# Knives_Controls.net
KiCad netlist of a schematic drawn in EAGLE
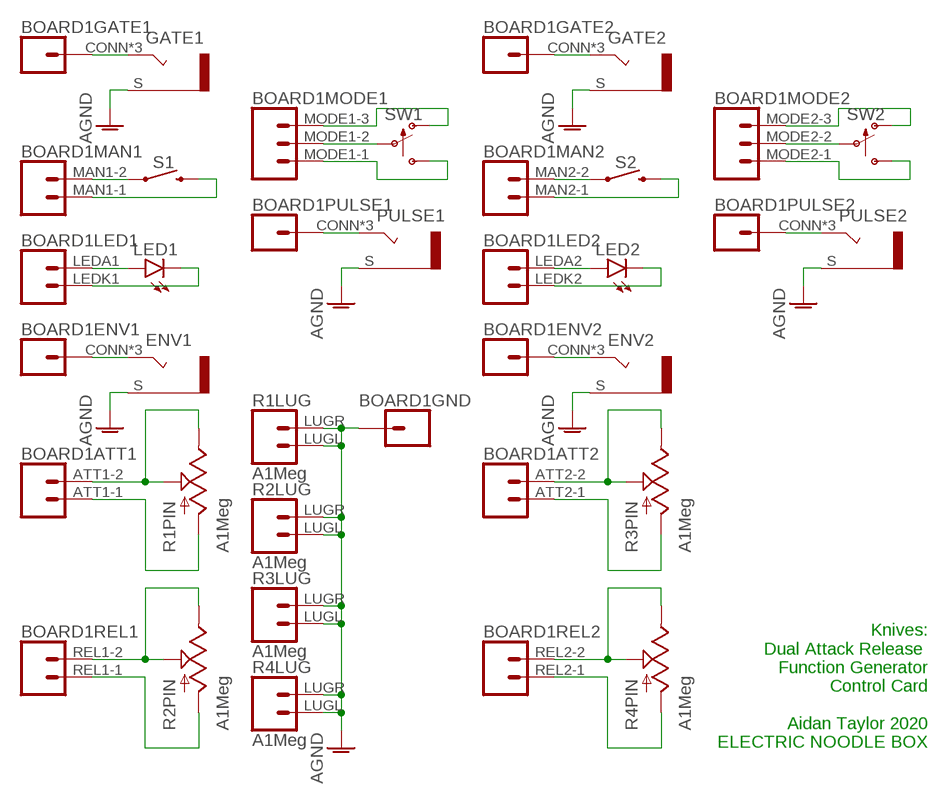
[diagram p0: schematic, sheet 1]

(export (version "E")
  (design (tool "Eeschema 10.0.6"))
  (components
    (comp (ref "BOARD1")
      (value "KNIVES_LINK")
      (footprint "eagle-import:KNIVES")
      (libsource (lib "eagle-import") (part "KNIVES_LINK"))
    )
    (comp (ref "ENV1")
      (value "COMBI-JACKCINCHNANA")
      (footprint "eagle-import:NEWCOMBOJACK_PANEL")
      (libsource (lib "eagle-import") (part "COMBI-JACKCINCHNANA"))
    )
    (comp (ref "ENV2")
      (value "COMBI-JACKCINCHNANA")
      (footprint "eagle-import:NEWCOMBOJACK_PANEL")
      (libsource (lib "eagle-import") (part "COMBI-JACKCINCHNANA"))
    )
    (comp (ref "GATE1")
      (value "COMBI-JACKCINCHNANA")
      (footprint "eagle-import:NEWCOMBOJACK_PANEL")
      (libsource (lib "eagle-import") (part "COMBI-JACKCINCHNANA"))
    )
    (comp (ref "GATE2")
      (value "COMBI-JACKCINCHNANA")
      (footprint "eagle-import:NEWCOMBOJACK_PANEL")
      (libsource (lib "eagle-import") (part "COMBI-JACKCINCHNANA"))
    )
    (comp (ref "LED1")
      (value "LED3MM")
      (footprint "eagle-import:LED3MM")
      (libsource (lib "eagle-import") (part "LED3MM"))
    )
    (comp (ref "LED2")
      (value "LED3MM")
      (footprint "eagle-import:LED3MM")
      (libsource (lib "eagle-import") (part "LED3MM"))
    )
    (comp (ref "PULSE1")
      (value "COMBI-JACKCINCHNANA")
      (footprint "eagle-import:NEWCOMBOJACK_PANEL")
      (libsource (lib "eagle-import") (part "COMBI-JACKCINCHNANA"))
    )
    (comp (ref "PULSE2")
      (value "COMBI-JACKCINCHNANA")
      (footprint "eagle-import:NEWCOMBOJACK_PANEL")
      (libsource (lib "eagle-import") (part "COMBI-JACKCINCHNANA"))
    )
    (comp (ref "R1")
      (value "A1Meg")
      (footprint "eagle-import:ALPHA_RV09_9MMPOT")
      (libsource (lib "eagle-import") (part "POTENTIOMETER"))
    )
    (comp (ref "R2")
      (value "A1Meg")
      (footprint "eagle-import:ALPHA_RV09_9MMPOT")
      (libsource (lib "eagle-import") (part "POTENTIOMETER"))
    )
    (comp (ref "R3")
      (value "A1Meg")
      (footprint "eagle-import:ALPHA_RV09_9MMPOT")
      (libsource (lib "eagle-import") (part "POTENTIOMETER"))
    )
    (comp (ref "R4")
      (value "A1Meg")
      (footprint "eagle-import:ALPHA_RV09_9MMPOT")
      (libsource (lib "eagle-import") (part "POTENTIOMETER"))
    )
    (comp (ref "S1")
      (value "MCDTS-2_PUSHBUTTON")
      (footprint "eagle-import:MCDTS-2_PUSHBUTTON")
      (libsource (lib "eagle-import") (part "MCDTS-2_PUSHBUTTON"))
    )
    (comp (ref "S2")
      (value "MCDTS-2_PUSHBUTTON")
      (footprint "eagle-import:MCDTS-2_PUSHBUTTON")
      (libsource (lib "eagle-import") (part "MCDTS-2_PUSHBUTTON"))
    )
    (comp (ref "SW1")
      (value "SPDT_SWITCHDW1")
      (footprint "eagle-import:MICRODPDT-DW1")
      (libsource (lib "eagle-import") (part "SPDT_SWITCHDW1"))
    )
    (comp (ref "SW2")
      (value "SPDT_SWITCHDW1")
      (footprint "eagle-import:MICRODPDT-DW1")
      (libsource (lib "eagle-import") (part "SPDT_SWITCHDW1"))
    )
  )
  (nets
    (net (code "1") (name "AGND") (class "Default")
      (node (ref "BOARD1") (pin "GND") (pinfunction "1_GND") (pintype "passive"))
      (node (ref "ENV1") (pin "S") (pinfunction "S_S") (pintype "passive"))
      (node (ref "ENV2") (pin "S") (pinfunction "S_S") (pintype "passive"))
      (node (ref "GATE1") (pin "S") (pinfunction "S_S") (pintype "passive"))
      (node (ref "GATE2") (pin "S") (pinfunction "S_S") (pintype "passive"))
      (node (ref "PULSE1") (pin "S") (pinfunction "S_S") (pintype "passive"))
      (node (ref "PULSE2") (pin "S") (pinfunction "S_S") (pintype "passive"))
      (node (ref "R1") (pin "LUGL") (pinfunction "1_LUGL") (pintype "passive"))
      (node (ref "R1") (pin "LUGR") (pinfunction "2_LUGR") (pintype "passive"))
      (node (ref "R2") (pin "LUGL") (pinfunction "1_LUGL") (pintype "passive"))
      (node (ref "R2") (pin "LUGR") (pinfunction "2_LUGR") (pintype "passive"))
      (node (ref "R3") (pin "LUGL") (pinfunction "1_LUGL") (pintype "passive"))
      (node (ref "R3") (pin "LUGR") (pinfunction "2_LUGR") (pintype "passive"))
      (node (ref "R4") (pin "LUGL") (pinfunction "1_LUGL") (pintype "passive"))
      (node (ref "R4") (pin "LUGR") (pinfunction "2_LUGR") (pintype "passive"))
    )
    (net (code "2") (name "Net-(BOARD1A-1)") (class "Default")
      (node (ref "BOARD1") (pin "ATT1-1") (pinfunction "1_ATT1-1") (pintype "passive"))
      (node (ref "R1") (pin "C1") (pinfunction "A_C1") (pintype "passive"))
    )
    (net (code "3") (name "Net-(BOARD1A-2)") (class "Default")
      (node (ref "BOARD1") (pin "ATT1-2") (pinfunction "2_ATT1-2") (pintype "passive"))
      (node (ref "R1") (pin "C2") (pinfunction "W_C2") (pintype "passive"))
      (node (ref "R1") (pin "C3") (pinfunction "B_C3") (pintype "passive"))
    )
    (net (code "4") (name "Net-(BOARD1B-1)") (class "Default")
      (node (ref "BOARD1") (pin "ATT2-1") (pinfunction "1_ATT2-1") (pintype "passive"))
      (node (ref "R3") (pin "C1") (pinfunction "A_C1") (pintype "passive"))
    )
    (net (code "5") (name "Net-(BOARD1B-2)") (class "Default")
      (node (ref "BOARD1") (pin "ATT2-2") (pinfunction "2_ATT2-2") (pintype "passive"))
      (node (ref "R3") (pin "C2") (pinfunction "W_C2") (pintype "passive"))
      (node (ref "R3") (pin "C3") (pinfunction "B_C3") (pintype "passive"))
    )
    (net (code "6") (name "Net-(BOARD1C-1)") (class "Default")
      (node (ref "BOARD1") (pin "EOUT1") (pinfunction "1_EOUT1") (pintype "passive"))
      (node (ref "ENV1") (pin "CONN") (pinfunction "T_CONN") (pintype "passive"))
      (node (ref "ENV1") (pin "T1") (pinfunction "T_T1") (pintype "passive"))
      (node (ref "ENV1") (pin "T2") (pinfunction "T_T2") (pintype "passive"))
    )
    (net (code "7") (name "Net-(BOARD1D-1)") (class "Default")
      (node (ref "BOARD1") (pin "EOUT2") (pinfunction "1_EOUT2") (pintype "passive"))
      (node (ref "ENV2") (pin "CONN") (pinfunction "T_CONN") (pintype "passive"))
      (node (ref "ENV2") (pin "T1") (pinfunction "T_T1") (pintype "passive"))
      (node (ref "ENV2") (pin "T2") (pinfunction "T_T2") (pintype "passive"))
    )
    (net (code "8") (name "Net-(BOARD1E-1)") (class "Default")
      (node (ref "BOARD1") (pin "G1") (pinfunction "1_G1") (pintype "passive"))
      (node (ref "GATE1") (pin "CONN") (pinfunction "T_CONN") (pintype "passive"))
      (node (ref "GATE1") (pin "T1") (pinfunction "T_T1") (pintype "passive"))
      (node (ref "GATE1") (pin "T2") (pinfunction "T_T2") (pintype "passive"))
    )
    (net (code "9") (name "Net-(BOARD1F-1)") (class "Default")
      (node (ref "BOARD1") (pin "G2") (pinfunction "1_G2") (pintype "passive"))
      (node (ref "GATE2") (pin "CONN") (pinfunction "T_CONN") (pintype "passive"))
      (node (ref "GATE2") (pin "T1") (pinfunction "T_T1") (pintype "passive"))
      (node (ref "GATE2") (pin "T2") (pinfunction "T_T2") (pintype "passive"))
    )
    (net (code "10") (name "Net-(BOARD1H-1)") (class "Default")
      (node (ref "BOARD1") (pin "LEDK1") (pinfunction "1_LEDK1") (pintype "passive"))
      (node (ref "LED1") (pin "K") (pinfunction "C_K") (pintype "passive"))
    )
    (net (code "11") (name "Net-(BOARD1H-2)") (class "Default")
      (node (ref "BOARD1") (pin "LEDA1") (pinfunction "2_LEDA1") (pintype "passive"))
      (node (ref "LED1") (pin "A") (pinfunction "A_A") (pintype "passive"))
    )
    (net (code "12") (name "Net-(BOARD1I-1)") (class "Default")
      (node (ref "BOARD1") (pin "LEDK2") (pinfunction "1_LEDK2") (pintype "passive"))
      (node (ref "LED2") (pin "K") (pinfunction "C_K") (pintype "passive"))
    )
    (net (code "13") (name "Net-(BOARD1I-2)") (class "Default")
      (node (ref "BOARD1") (pin "LEDA2") (pinfunction "2_LEDA2") (pintype "passive"))
      (node (ref "LED2") (pin "A") (pinfunction "A_A") (pintype "passive"))
    )
    (net (code "14") (name "Net-(BOARD1J-1)") (class "Default")
      (node (ref "BOARD1") (pin "MAN1-1") (pinfunction "1_MAN1-1") (pintype "passive"))
      (node (ref "S1") (pin "P$3") (pinfunction "2_P$3") (pintype "passive"))
      (node (ref "S1") (pin "P$4") (pinfunction "2_P$4") (pintype "passive"))
    )
    (net (code "15") (name "Net-(BOARD1J-2)") (class "Default")
      (node (ref "BOARD1") (pin "MAN1-2") (pinfunction "2_MAN1-2") (pintype "passive"))
      (node (ref "S1") (pin "P$1") (pinfunction "1_P$1") (pintype "passive"))
      (node (ref "S1") (pin "P$2") (pinfunction "1_P$2") (pintype "passive"))
    )
    (net (code "16") (name "Net-(BOARD1K-1)") (class "Default")
      (node (ref "BOARD1") (pin "MAN2-1") (pinfunction "1_MAN2-1") (pintype "passive"))
      (node (ref "S2") (pin "P$3") (pinfunction "2_P$3") (pintype "passive"))
      (node (ref "S2") (pin "P$4") (pinfunction "2_P$4") (pintype "passive"))
    )
    (net (code "17") (name "Net-(BOARD1K-2)") (class "Default")
      (node (ref "BOARD1") (pin "MAN2-2") (pinfunction "2_MAN2-2") (pintype "passive"))
      (node (ref "S2") (pin "P$1") (pinfunction "1_P$1") (pintype "passive"))
      (node (ref "S2") (pin "P$2") (pinfunction "1_P$2") (pintype "passive"))
    )
    (net (code "18") (name "Net-(BOARD1L-1)") (class "Default")
      (node (ref "BOARD1") (pin "MODE1-1") (pinfunction "1_MODE1-1") (pintype "passive"))
      (node (ref "SW1") (pin "C3") (pinfunction "S_C3") (pintype "passive"))
    )
    (net (code "19") (name "Net-(BOARD1L-2)") (class "Default")
      (node (ref "BOARD1") (pin "MODE1-2") (pinfunction "2_MODE1-2") (pintype "passive"))
      (node (ref "SW1") (pin "C2") (pinfunction "P_C2") (pintype "passive"))
    )
    (net (code "20") (name "Net-(BOARD1L-3)") (class "Default")
      (node (ref "BOARD1") (pin "MODE1-3") (pinfunction "3_MODE1-3") (pintype "passive"))
      (node (ref "SW1") (pin "C1") (pinfunction "O_C1") (pintype "passive"))
    )
    (net (code "21") (name "Net-(BOARD1M-1)") (class "Default")
      (node (ref "BOARD1") (pin "MODE2-1") (pinfunction "1_MODE2-1") (pintype "passive"))
      (node (ref "SW2") (pin "C3") (pinfunction "S_C3") (pintype "passive"))
    )
    (net (code "22") (name "Net-(BOARD1M-2)") (class "Default")
      (node (ref "BOARD1") (pin "MODE2-2") (pinfunction "2_MODE2-2") (pintype "passive"))
      (node (ref "SW2") (pin "C2") (pinfunction "P_C2") (pintype "passive"))
    )
    (net (code "23") (name "Net-(BOARD1M-3)") (class "Default")
      (node (ref "BOARD1") (pin "MODE2-3") (pinfunction "3_MODE2-3") (pintype "passive"))
      (node (ref "SW2") (pin "C1") (pinfunction "O_C1") (pintype "passive"))
    )
    (net (code "24") (name "Net-(BOARD1N-1)") (class "Default")
      (node (ref "BOARD1") (pin "P1") (pinfunction "1_P1") (pintype "passive"))
      (node (ref "PULSE1") (pin "CONN") (pinfunction "T_CONN") (pintype "passive"))
      (node (ref "PULSE1") (pin "T1") (pinfunction "T_T1") (pintype "passive"))
      (node (ref "PULSE1") (pin "T2") (pinfunction "T_T2") (pintype "passive"))
    )
    (net (code "25") (name "Net-(BOARD1O-1)") (class "Default")
      (node (ref "BOARD1") (pin "P2") (pinfunction "1_P2") (pintype "passive"))
      (node (ref "PULSE2") (pin "CONN") (pinfunction "T_CONN") (pintype "passive"))
      (node (ref "PULSE2") (pin "T1") (pinfunction "T_T1") (pintype "passive"))
      (node (ref "PULSE2") (pin "T2") (pinfunction "T_T2") (pintype "passive"))
    )
    (net (code "26") (name "Net-(BOARD1P-1)") (class "Default")
      (node (ref "BOARD1") (pin "REL1-1") (pinfunction "1_REL1-1") (pintype "passive"))
      (node (ref "R2") (pin "C1") (pinfunction "A_C1") (pintype "passive"))
    )
    (net (code "27") (name "Net-(BOARD1P-2)") (class "Default")
      (node (ref "BOARD1") (pin "REL1-2") (pinfunction "2_REL1-2") (pintype "passive"))
      (node (ref "R2") (pin "C2") (pinfunction "W_C2") (pintype "passive"))
      (node (ref "R2") (pin "C3") (pinfunction "B_C3") (pintype "passive"))
    )
    (net (code "28") (name "Net-(BOARD1Q-1)") (class "Default")
      (node (ref "BOARD1") (pin "REL2-1") (pinfunction "1_REL2-1") (pintype "passive"))
      (node (ref "R4") (pin "C1") (pinfunction "A_C1") (pintype "passive"))
    )
    (net (code "29") (name "Net-(BOARD1Q-2)") (class "Default")
      (node (ref "BOARD1") (pin "REL2-2") (pinfunction "2_REL2-2") (pintype "passive"))
      (node (ref "R4") (pin "C2") (pinfunction "W_C2") (pintype "passive"))
      (node (ref "R4") (pin "C3") (pinfunction "B_C3") (pintype "passive"))
    )
  )
)
